# design.net
KiCad netlist of a schematic drawn in Altium Designer
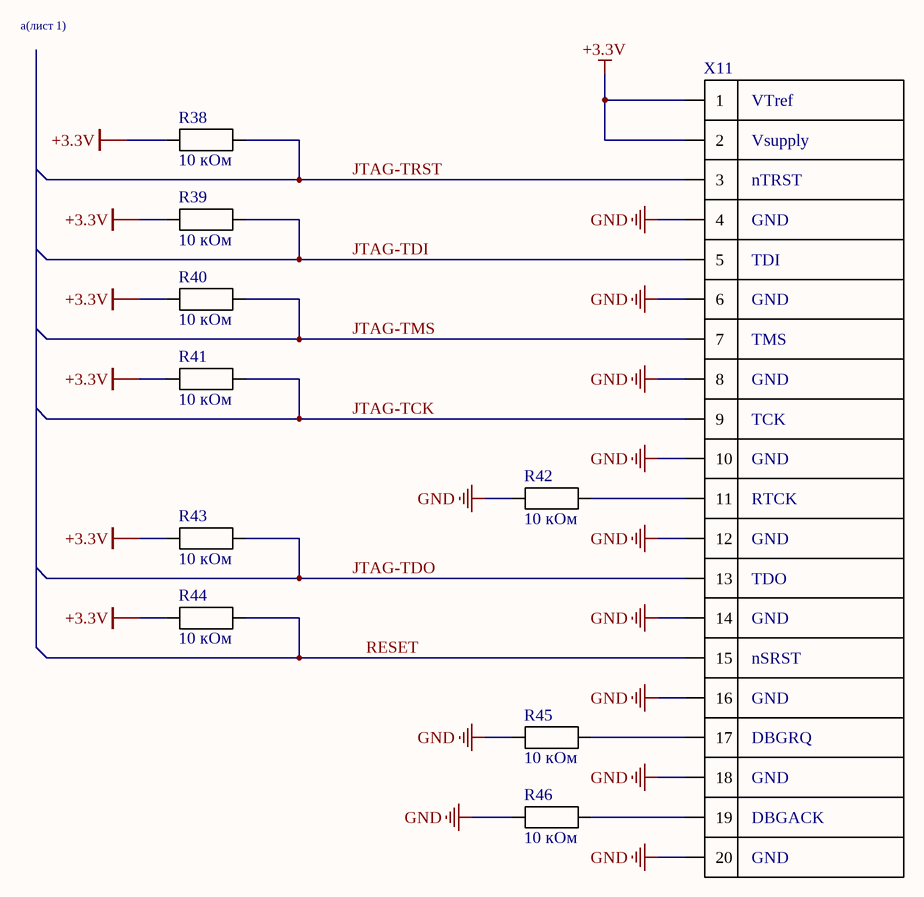
[diagram p0: Разъем программирования.SchDoc]

(export (version "E")
  (design (tool "Eeschema 10.0.6"))
  (components
    (comp (ref "R38")
      (value "10 кОм")
      (footprint "Р1-12-0,125")
      (fields
        (field (name "TOLERANCE") "±1%-Л")
        (field (name "PARTNUMBER") "АЛЯР.434110.005 ТУ")
        (field (name "MANUFACTURERPARTNUMBER") "Р1-12-0,125-10,0 кОм±1%-Л")
      )
      (libsource (lib "РЕЗИСТОРЫ") (part "Р1-12-0,125-10,0 кОм±1%"))
    )
    (comp (ref "R39")
      (value "10 кОм")
      (footprint "Р1-12-0,125")
      (fields
        (field (name "TOLERANCE") "±1%-Л")
        (field (name "PARTNUMBER") "АЛЯР.434110.005 ТУ")
        (field (name "MANUFACTURERPARTNUMBER") "Р1-12-0,125-10,0 кОм±1%-Л")
      )
      (libsource (lib "РЕЗИСТОРЫ") (part "Р1-12-0,125-10,0 кОм±1%"))
    )
    (comp (ref "R40")
      (value "10 кОм")
      (footprint "Р1-12-0,125")
      (fields
        (field (name "TOLERANCE") "±1%-Л")
        (field (name "PARTNUMBER") "АЛЯР.434110.005 ТУ")
        (field (name "MANUFACTURERPARTNUMBER") "Р1-12-0,125-10,0 кОм±1%-Л")
      )
      (libsource (lib "РЕЗИСТОРЫ") (part "Р1-12-0,125-10,0 кОм±1%"))
    )
    (comp (ref "R41")
      (value "10 кОм")
      (footprint "Р1-12-0,125")
      (fields
        (field (name "TOLERANCE") "±1%-Л")
        (field (name "PARTNUMBER") "АЛЯР.434110.005 ТУ")
        (field (name "MANUFACTURERPARTNUMBER") "Р1-12-0,125-10,0 кОм±1%-Л")
      )
      (libsource (lib "РЕЗИСТОРЫ") (part "Р1-12-0,125-10,0 кОм±1%"))
    )
    (comp (ref "R42")
      (value "10 кОм")
      (footprint "Р1-12-0,125")
      (fields
        (field (name "TOLERANCE") "±1%-Л")
        (field (name "PARTNUMBER") "АЛЯР.434110.005 ТУ")
        (field (name "MANUFACTURERPARTNUMBER") "Р1-12-0,125-10,0 кОм±1%-Л")
      )
      (libsource (lib "РЕЗИСТОРЫ") (part "Р1-12-0,125-10,0 кОм±1%"))
    )
    (comp (ref "R43")
      (value "10 кОм")
      (footprint "Р1-12-0,125")
      (fields
        (field (name "TOLERANCE") "±1%-Л")
        (field (name "PARTNUMBER") "АЛЯР.434110.005 ТУ")
        (field (name "MANUFACTURERPARTNUMBER") "Р1-12-0,125-10,0 кОм±1%-Л")
      )
      (libsource (lib "РЕЗИСТОРЫ") (part "Р1-12-0,125-10,0 кОм±1%"))
    )
    (comp (ref "R44")
      (value "10 кОм")
      (footprint "Р1-12-0,125")
      (fields
        (field (name "TOLERANCE") "±1%-Л")
        (field (name "PARTNUMBER") "АЛЯР.434110.005 ТУ")
        (field (name "MANUFACTURERPARTNUMBER") "Р1-12-0,125-10,0 кОм±1%-Л")
      )
      (libsource (lib "РЕЗИСТОРЫ") (part "Р1-12-0,125-10,0 кОм±1%"))
    )
    (comp (ref "R45")
      (value "10 кОм")
      (footprint "Р1-12-0,125")
      (fields
        (field (name "TOLERANCE") "±1%-Л")
        (field (name "PARTNUMBER") "АЛЯР.434110.005 ТУ")
        (field (name "MANUFACTURERPARTNUMBER") "Р1-12-0,125-10,0 кОм±1%-Л")
      )
      (libsource (lib "РЕЗИСТОРЫ") (part "Р1-12-0,125-10,0 кОм±1%"))
    )
    (comp (ref "R46")
      (value "10 кОм")
      (footprint "Р1-12-0,125")
      (fields
        (field (name "TOLERANCE") "±1%-Л")
        (field (name "PARTNUMBER") "АЛЯР.434110.005 ТУ")
        (field (name "MANUFACTURERPARTNUMBER") "Р1-12-0,125-10,0 кОм±1%-Л")
      )
      (libsource (lib "РЕЗИСТОРЫ") (part "Р1-12-0,125-10,0 кОм±1%"))
    )
    (comp (ref "X11")
      (value "~")
      (footprint "IDC20MS")
      (fields
        (field (name "PARTNUMBER") "РЮМК.430420.033 ТУ")
        (field (name "MANUFACTURERPARTNUMBER") "Вилка СНП394-20ВП21-2")
      )
      (libsource (lib "РАЗЪЕМЫ") (part "SAM_ICE_RUS_20"))
    )
  )
  (nets
    (net (code "1") (name "+3.3V") (class "Default")
      (node (ref "R38") (pin "1") (pinfunction "1_1") (pintype "passive"))
      (node (ref "R39") (pin "1") (pinfunction "1_1") (pintype "passive"))
      (node (ref "R40") (pin "1") (pinfunction "1_1") (pintype "passive"))
      (node (ref "R41") (pin "1") (pinfunction "1_1") (pintype "passive"))
      (node (ref "R43") (pin "1") (pinfunction "1_1") (pintype "passive"))
      (node (ref "R44") (pin "1") (pinfunction "1_1") (pintype "passive"))
      (node (ref "X11") (pin "1") (pinfunction "1_1") (pintype "passive"))
      (node (ref "X11") (pin "2") (pinfunction "2_2") (pintype "passive"))
    )
    (net (code "2") (name "/JTAG-TCK") (class "Default")
      (node (ref "R41") (pin "2") (pinfunction "2_2") (pintype "passive"))
      (node (ref "X11") (pin "9") (pinfunction "9_9") (pintype "passive"))
    )
    (net (code "3") (name "/JTAG-TDI") (class "Default")
      (node (ref "R39") (pin "2") (pinfunction "2_2") (pintype "passive"))
      (node (ref "X11") (pin "5") (pinfunction "5_5") (pintype "passive"))
    )
    (net (code "4") (name "/JTAG-TDO") (class "Default")
      (node (ref "R43") (pin "2") (pinfunction "2_2") (pintype "passive"))
      (node (ref "X11") (pin "13") (pinfunction "13_13") (pintype "passive"))
    )
    (net (code "5") (name "/JTAG-TMS") (class "Default")
      (node (ref "R40") (pin "2") (pinfunction "2_2") (pintype "passive"))
      (node (ref "X11") (pin "7") (pinfunction "7_7") (pintype "passive"))
    )
    (net (code "6") (name "/JTAG-TRST") (class "Default")
      (node (ref "R38") (pin "2") (pinfunction "2_2") (pintype "passive"))
      (node (ref "X11") (pin "3") (pinfunction "3_3") (pintype "passive"))
    )
    (net (code "7") (name "/RESET") (class "Default")
      (node (ref "R44") (pin "2") (pinfunction "2_2") (pintype "passive"))
      (node (ref "X11") (pin "15") (pinfunction "15_15") (pintype "passive"))
    )
    (net (code "8") (name "GND") (class "Default")
      (node (ref "R42") (pin "1") (pinfunction "1_1") (pintype "passive"))
      (node (ref "R45") (pin "1") (pinfunction "1_1") (pintype "passive"))
      (node (ref "R46") (pin "1") (pinfunction "1_1") (pintype "passive"))
      (node (ref "X11") (pin "10") (pinfunction "10_10") (pintype "passive"))
      (node (ref "X11") (pin "12") (pinfunction "12_12") (pintype "passive"))
      (node (ref "X11") (pin "14") (pinfunction "14_14") (pintype "passive"))
      (node (ref "X11") (pin "16") (pinfunction "16_16") (pintype "passive"))
      (node (ref "X11") (pin "18") (pinfunction "18_18") (pintype "passive"))
      (node (ref "X11") (pin "20") (pinfunction "20_20") (pintype "passive"))
      (node (ref "X11") (pin "4") (pinfunction "4_4") (pintype "passive"))
      (node (ref "X11") (pin "6") (pinfunction "6_6") (pintype "passive"))
      (node (ref "X11") (pin "8") (pinfunction "8_8") (pintype "passive"))
    )
    (net (code "9") (name "Net-(R42-Pad2)") (class "Default")
      (node (ref "R42") (pin "2") (pinfunction "2_2") (pintype "passive"))
      (node (ref "X11") (pin "11") (pinfunction "11_11") (pintype "passive"))
    )
    (net (code "10") (name "Net-(R45-Pad2)") (class "Default")
      (node (ref "R45") (pin "2") (pinfunction "2_2") (pintype "passive"))
      (node (ref "X11") (pin "17") (pinfunction "17_17") (pintype "passive"))
    )
    (net (code "11") (name "Net-(R46-Pad2)") (class "Default")
      (node (ref "R46") (pin "2") (pinfunction "2_2") (pintype "passive"))
      (node (ref "X11") (pin "19") (pinfunction "19_19") (pintype "passive"))
    )
  )
)
